# MCU_RP2350.net
KiCad netlist of a schematic drawn in Altium Designer
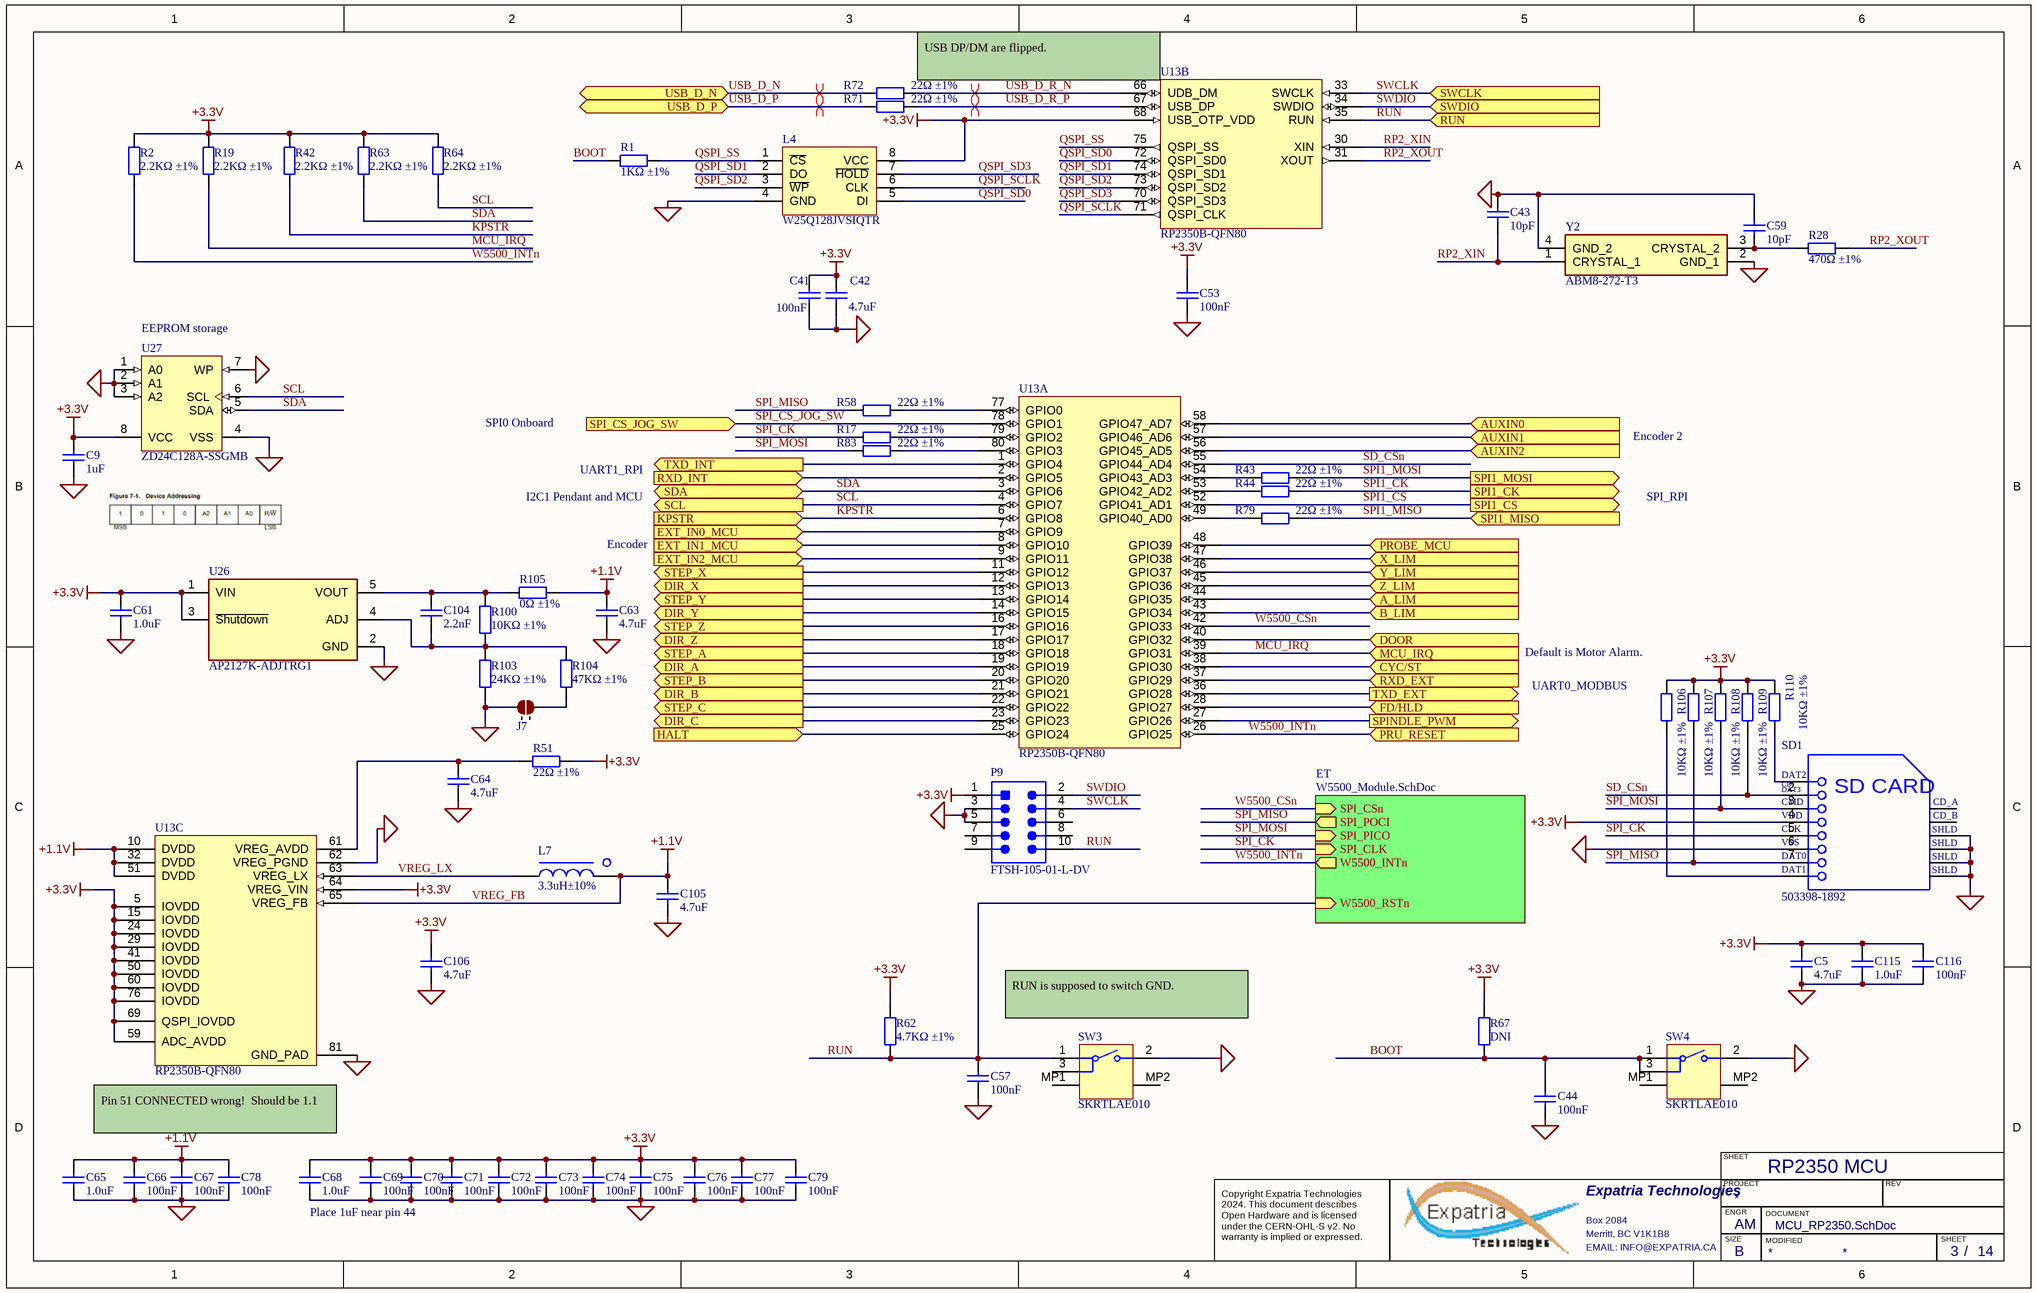
[diagram p0: MCU_RP2350.SchDoc]

(export (version "E")
  (design (tool "Eeschema 10.0.6"))
  (components
    (comp (ref "C5")
      (value "4.7uF")
      (footprint "0603_C")
      (description "16V 4.7uF X5R ±10% 0603 Multilayer Ceramic Capacitors MLCC - SMD/SMT ROHS")
      (fields (field (name "MANUFACTURER") "Samsung Electro-Mechanics") (field (name "TOLERANCE") "10%"))
      (libsource (lib "Sienci_Labs") (part "0603 4.7uF (475) 10% 16V"))
    )
    (comp (ref "C9")
      (value "1uF")
      (footprint "0603_C")
      (description "Chip capacitors")
      (fields
        (field (name "MANUFACTURER") "Samsung Electro-Mechanics")
        (field (name "PARTNUMBER") "CL10A105KB8NNNC")
      )
      (libsource (lib "Cap") (part "0603 1uF (105) 10% 50V"))
    )
    (comp (ref "C41")
      (value "100nF")
      (footprint "0402_C")
      (description "Chip capacitors")
      (fields
        (field (name "MANUFACTURER") "Samsung Electro-Mechanics")
        (field (name "PARTNUMBER") "CL05B104KO5NNNC")
      )
      (libsource (lib "Cap") (part "0402 100nF (104) 10% 16V"))
    )
    (comp (ref "C42")
      (value "4.7uF")
      (footprint "0402_C")
      (description "Chip capacitor")
      (fields
        (field (name "MANUFACTURER") "Samsung Electro-Mechanics")
        (field (name "PARTNUMBER") "CL05A475MP5NRNC")
      )
      (libsource (lib "Cap") (part "0402 4.7uF (475) 20% 10V"))
    )
    (comp (ref "C43")
      (value "10pF")
      (footprint "0402_C")
      (description "Chip capacitors")
      (fields
        (field (name "MANUFACTURER") "Samsung Electro-Mechanics")
        (field (name "PARTNUMBER") "CL05C100JB5NNNC")
      )
      (libsource (lib "Cap") (part "0402 10pF (100) 5% 50V"))
    )
    (comp (ref "C44")
      (value "100nF")
      (footprint "0402_C")
      (description "Chip capacitors")
      (fields
        (field (name "MANUFACTURER") "Samsung Electro-Mechanics")
        (field (name "PARTNUMBER") "CL05B104KO5NNNC")
      )
      (libsource (lib "Cap") (part "0402 100nF (104) 10% 16V"))
    )
    (comp (ref "C53")
      (value "100nF")
      (footprint "0402_C")
      (description "Chip capacitors")
      (fields
        (field (name "MANUFACTURER") "Samsung Electro-Mechanics")
        (field (name "PARTNUMBER") "CL05B104KO5NNNC")
      )
      (libsource (lib "Cap") (part "0402 100nF (104) 10% 16V"))
    )
    (comp (ref "C57")
      (value "100nF")
      (footprint "0402_C")
      (description "Chip capacitors")
      (fields
        (field (name "MANUFACTURER") "Samsung Electro-Mechanics")
        (field (name "PARTNUMBER") "CL05B104KO5NNNC")
      )
      (libsource (lib "Cap") (part "0402 100nF (104) 10% 16V"))
    )
    (comp (ref "C59")
      (value "10pF")
      (footprint "0402_C")
      (description "Chip capacitors")
      (fields
        (field (name "MANUFACTURER") "Samsung Electro-Mechanics")
        (field (name "PARTNUMBER") "CL05C100JB5NNNC")
      )
      (libsource (lib "Cap") (part "0402 10pF (100) 5% 50V"))
    )
    (comp (ref "C61")
      (value "1.0uF")
      (footprint "0402_C")
      (description "Chip capacitor")
      (fields
        (field (name "MANUFACTURER") "Samsung Electro-Mechanics")
        (field (name "PARTNUMBER") "CL05A105KA5NQNC")
      )
      (libsource (lib "Cap") (part "0402 1.0uF (105) 10% 25V"))
    )
    (comp (ref "C63")
      (value "4.7uF")
      (footprint "0402_C")
      (description "Chip capacitor")
      (fields
        (field (name "MANUFACTURER") "Samsung Electro-Mechanics")
        (field (name "PARTNUMBER") "CL05A475MP5NRNC")
      )
      (libsource (lib "Cap") (part "0402 4.7uF (475) 20% 10V"))
    )
    (comp (ref "C64")
      (value "4.7uF")
      (footprint "0402_C")
      (description "Chip capacitor")
      (fields
        (field (name "MANUFACTURER") "Samsung Electro-Mechanics")
        (field (name "PARTNUMBER") "CL05A475MP5NRNC")
      )
      (libsource (lib "Cap") (part "0402 4.7uF (475) 20% 10V"))
    )
    (comp (ref "C65")
      (value "1.0uF")
      (footprint "0402_C")
      (description "Chip capacitor")
      (fields
        (field (name "MANUFACTURER") "Samsung Electro-Mechanics")
        (field (name "PARTNUMBER") "CL05A105KA5NQNC")
      )
      (libsource (lib "Cap") (part "0402 1.0uF (105) 10% 25V"))
    )
    (comp (ref "C66")
      (value "100nF")
      (footprint "0402_C")
      (description "Chip capacitors")
      (fields
        (field (name "MANUFACTURER") "Samsung Electro-Mechanics")
        (field (name "PARTNUMBER") "CL05B104KO5NNNC")
      )
      (libsource (lib "Cap") (part "0402 100nF (104) 10% 16V"))
    )
    (comp (ref "C67")
      (value "100nF")
      (footprint "0402_C")
      (description "Chip capacitors")
      (fields
        (field (name "MANUFACTURER") "Samsung Electro-Mechanics")
        (field (name "PARTNUMBER") "CL05B104KO5NNNC")
      )
      (libsource (lib "Cap") (part "0402 100nF (104) 10% 16V"))
    )
    (comp (ref "C68")
      (value "1.0uF")
      (footprint "0402_C")
      (description "Chip capacitor")
      (fields
        (field (name "MANUFACTURER") "Samsung Electro-Mechanics")
        (field (name "PARTNUMBER") "CL05A105KA5NQNC")
      )
      (libsource (lib "Cap") (part "0402 1.0uF (105) 10% 25V"))
    )
    (comp (ref "C69")
      (value "100nF")
      (footprint "0402_C")
      (description "Chip capacitors")
      (fields
        (field (name "MANUFACTURER") "Samsung Electro-Mechanics")
        (field (name "PARTNUMBER") "CL05B104KO5NNNC")
      )
      (libsource (lib "Cap") (part "0402 100nF (104) 10% 16V"))
    )
    (comp (ref "C70")
      (value "100nF")
      (footprint "0402_C")
      (description "Chip capacitors")
      (fields
        (field (name "MANUFACTURER") "Samsung Electro-Mechanics")
        (field (name "PARTNUMBER") "CL05B104KO5NNNC")
      )
      (libsource (lib "Cap") (part "0402 100nF (104) 10% 16V"))
    )
    (comp (ref "C71")
      (value "100nF")
      (footprint "0402_C")
      (description "Chip capacitors")
      (fields
        (field (name "MANUFACTURER") "Samsung Electro-Mechanics")
        (field (name "PARTNUMBER") "CL05B104KO5NNNC")
      )
      (libsource (lib "Cap") (part "0402 100nF (104) 10% 16V"))
    )
    (comp (ref "C72")
      (value "100nF")
      (footprint "0402_C")
      (description "Chip capacitors")
      (fields
        (field (name "MANUFACTURER") "Samsung Electro-Mechanics")
        (field (name "PARTNUMBER") "CL05B104KO5NNNC")
      )
      (libsource (lib "Cap") (part "0402 100nF (104) 10% 16V"))
    )
    (comp (ref "C73")
      (value "100nF")
      (footprint "0402_C")
      (description "Chip capacitors")
      (fields
        (field (name "MANUFACTURER") "Samsung Electro-Mechanics")
        (field (name "PARTNUMBER") "CL05B104KO5NNNC")
      )
      (libsource (lib "Cap") (part "0402 100nF (104) 10% 16V"))
    )
    (comp (ref "C74")
      (value "100nF")
      (footprint "0402_C")
      (description "Chip capacitors")
      (fields
        (field (name "MANUFACTURER") "Samsung Electro-Mechanics")
        (field (name "PARTNUMBER") "CL05B104KO5NNNC")
      )
      (libsource (lib "Cap") (part "0402 100nF (104) 10% 16V"))
    )
    (comp (ref "C75")
      (value "100nF")
      (footprint "0402_C")
      (description "Chip capacitors")
      (fields
        (field (name "MANUFACTURER") "Samsung Electro-Mechanics")
        (field (name "PARTNUMBER") "CL05B104KO5NNNC")
      )
      (libsource (lib "Cap") (part "0402 100nF (104) 10% 16V"))
    )
    (comp (ref "C76")
      (value "100nF")
      (footprint "0402_C")
      (description "Chip capacitors")
      (fields
        (field (name "MANUFACTURER") "Samsung Electro-Mechanics")
        (field (name "PARTNUMBER") "CL05B104KO5NNNC")
      )
      (libsource (lib "Cap") (part "0402 100nF (104) 10% 16V"))
    )
    (comp (ref "C77")
      (value "100nF")
      (footprint "0402_C")
      (description "Chip capacitors")
      (fields
        (field (name "MANUFACTURER") "Samsung Electro-Mechanics")
        (field (name "PARTNUMBER") "CL05B104KO5NNNC")
      )
      (libsource (lib "Cap") (part "0402 100nF (104) 10% 16V"))
    )
    (comp (ref "C78")
      (value "100nF")
      (footprint "0402_C")
      (description "Chip capacitors")
      (fields
        (field (name "MANUFACTURER") "Samsung Electro-Mechanics")
        (field (name "PARTNUMBER") "CL05B104KO5NNNC")
      )
      (libsource (lib "Cap") (part "0402 100nF (104) 10% 16V"))
    )
    (comp (ref "C79")
      (value "100nF")
      (footprint "0402_C")
      (description "Chip capacitors")
      (fields
        (field (name "MANUFACTURER") "Samsung Electro-Mechanics")
        (field (name "PARTNUMBER") "CL05B104KO5NNNC")
      )
      (libsource (lib "Cap") (part "0402 100nF (104) 10% 16V"))
    )
    (comp (ref "C104")
      (value "2.2nF")
      (footprint "0402_C")
      (description "Chip capacitor")
      (fields
        (field (name "MANUFACTURER") "Guangdong Fenghua Advanced Tech")
        (field (name "PARTNUMBER") "0402B222K500NT")
      )
      (libsource (lib "Cap") (part "0402 2.2nF (222) 10% 50V"))
    )
    (comp (ref "C105")
      (value "4.7uF")
      (footprint "0402_C - wide")
      (description "Chip capacitor")
      (fields
        (field (name "MANUFACTURER") "Samsung Electro-Mechanics")
        (field (name "PARTNUMBER") "CL05A475MP5NRNC")
      )
      (libsource (lib "Cap") (part "0402 4.7uF (475) 20% 10V"))
    )
    (comp (ref "C106")
      (value "4.7uF")
      (footprint "0402_C - wide")
      (description "Chip capacitor")
      (fields
        (field (name "MANUFACTURER") "Samsung Electro-Mechanics")
        (field (name "PARTNUMBER") "CL05A475MP5NRNC")
      )
      (libsource (lib "Cap") (part "0402 4.7uF (475) 20% 10V"))
    )
    (comp (ref "C115")
      (value "1.0uF")
      (footprint "0402_C")
      (description "Chip capacitor")
      (fields (field (name "MANUFACTURER") "Samsung Electro-Mechanics") (field (name "TOLERANCE") "10%"))
      (libsource (lib "Cap") (part "0402 1.0uF (105) 10% 25V"))
    )
    (comp (ref "C116")
      (value "100nF")
      (footprint "0402_C")
      (description "16V 100nF X7R ±10% 0402 Multilayer Ceramic Capacitors MLCC - SMD/SMT ROHS")
      (fields (field (name "MANUFACTURER") "Samsung Electro-Mechanics") (field (name "TOLERANCE") "10%"))
      (libsource (lib "Sienci_Labs") (part "0402 100nF (104) 10% 16V"))
    )
    (comp (ref "J7")
      (value "2 way net solder junction - Normally Open")
      (footprint "2waySolder_NO")
      (libsource (lib "NetTie") (part "2waySolderNO"))
    )
    (comp (ref "L4")
      (value "W25Q128JVSIQTR")
      (footprint "SOIC-8_208mil")
      (description "Flash ROM")
      (libsource (lib "IC") (part "W25Q128JVSIQTR_[C97521]"))
    )
    (comp (ref "L7")
      (value "3.3uH±10%")
      (footprint "0806_L_POL")
      (description "贴片电感")
      (libsource (lib "IUD") (part "0806 3.3uH Polarized RP2350"))
    )
    (comp (ref "P9")
      (value "FTSH-105-01-L-DV")
      (footprint "SMTC-FTSH-105-01-L-DV_V")
      (description "Male Header, Pitch 1.27 mm, 2 x 5 Position, Height 5.96 mm, -55 to 125 degC, RoHS, Bulk")
      (fields (field (name "MANUFACTURER") "Samtec"))
      (libsource (lib "Altium Content Vault") (part "CN-2P-M-R10"))
    )
    (comp (ref "R1")
      (value "1KΩ ±1%")
      (footprint "0402_R")
      (description "Chip resistor")
      (fields (field (name "MANUFACTURER") "Uniroyal Elec") (field (name "PARTNUMBER") "0402WGF1001TCE"))
      (libsource (lib "RES") (part "0402 1K (1001) 1%"))
    )
    (comp (ref "R2")
      (value "2.2KΩ ±1%")
      (footprint "0402_R")
      (description "Chip resistor")
      (fields (field (name "MANUFACTURER") "Uniroyal Elec") (field (name "PARTNUMBER") "0402WGF2201TCE"))
      (libsource (lib "RES") (part "0402 2.2K (2201) 1%"))
    )
    (comp (ref "R17")
      (value "22Ω ±1%")
      (footprint "0402_R")
      (description "Chip resistor")
      (fields (field (name "MANUFACTURER") "Uniroyal Elec") (field (name "PARTNUMBER") "0402WGF220JTCE"))
      (libsource (lib "") (part "0402 22R (22R0) 1%_2"))
    )
    (comp (ref "R19")
      (value "2.2KΩ ±1%")
      (footprint "0402_R")
      (description "Chip resistor")
      (fields (field (name "MANUFACTURER") "Uniroyal Elec") (field (name "PARTNUMBER") "0402WGF2201TCE"))
      (libsource (lib "RES") (part "0402 2.2K (2201) 1%"))
    )
    (comp (ref "R28")
      (value "470Ω ±1%")
      (footprint "0402_R")
      (description "Chip resistor")
      (fields (field (name "MANUFACTURER") "Uniroyal Elec") (field (name "PARTNUMBER") "0402WGF4700TCE"))
      (libsource (lib "RES") (part "0402 470R (4700) 1%"))
    )
    (comp (ref "R42")
      (value "2.2KΩ ±1%")
      (footprint "0402_R")
      (description "Chip resistor")
      (fields (field (name "MANUFACTURER") "Uniroyal Elec") (field (name "PARTNUMBER") "0402WGF2201TCE"))
      (libsource (lib "RES") (part "0402 2.2K (2201) 1%"))
    )
    (comp (ref "R43")
      (value "22Ω ±1%")
      (footprint "0402_R")
      (description "Chip resistor")
      (fields (field (name "MANUFACTURER") "Uniroyal Elec") (field (name "PARTNUMBER") "0402WGF220JTCE"))
      (libsource (lib "") (part "0402 22R (22R0) 1%_2"))
    )
    (comp (ref "R44")
      (value "22Ω ±1%")
      (footprint "0402_R")
      (description "Chip resistor")
      (fields (field (name "MANUFACTURER") "Uniroyal Elec") (field (name "PARTNUMBER") "0402WGF220JTCE"))
      (libsource (lib "") (part "0402 22R (22R0) 1%_2"))
    )
    (comp (ref "R51")
      (value "22Ω ±1%")
      (footprint "0402_R")
      (description "Chip resistor")
      (fields (field (name "MANUFACTURER") "Uniroyal Elec") (field (name "PARTNUMBER") "0402WGF220JTCE"))
      (libsource (lib "RES") (part "0402 22R (22R0) 1%"))
    )
    (comp (ref "R58")
      (value "22Ω ±1%")
      (footprint "0402_R")
      (description "Chip resistor")
      (fields (field (name "MANUFACTURER") "Uniroyal Elec") (field (name "PARTNUMBER") "0402WGF220JTCE"))
      (libsource (lib "") (part "0402 22R (22R0) 1%_2"))
    )
    (comp (ref "R62")
      (value "4.7KΩ ±1%")
      (footprint "0402_R")
      (description "Chip resistor")
      (fields (field (name "MANUFACTURER") "Uniroyal Elec") (field (name "PARTNUMBER") "0402WGF4701TCE"))
      (libsource (lib "RES") (part "0402 4.7K (4701) 1%"))
    )
    (comp (ref "R63")
      (value "2.2KΩ ±1%")
      (footprint "0402_R")
      (description "Chip resistor")
      (fields (field (name "MANUFACTURER") "Uniroyal Elec") (field (name "PARTNUMBER") "0402WGF2201TCE"))
      (libsource (lib "RES") (part "0402 2.2K (2201) 1%"))
    )
    (comp (ref "R64")
      (value "2.2KΩ ±1%")
      (footprint "0402_R")
      (description "Chip resistor")
      (fields (field (name "MANUFACTURER") "Uniroyal Elec") (field (name "PARTNUMBER") "0402WGF2201TCE"))
      (libsource (lib "RES") (part "0402 2.2K (2201) 1%"))
    )
    (comp (ref "R67")
      (value "DNI")
      (footprint "0603_R")
      (description "Chip resistor")
      (fields (field (name "MANUFACTURER") "Uniroyal Elec") (field (name "PARTNUMBER") "0603WAF1002T5E"))
      (libsource (lib "RES") (part "0603 10K (1002) 1%"))
    )
    (comp (ref "R71")
      (value "22Ω ±1%")
      (footprint "0402_R")
      (description "Chip resistor")
      (fields (field (name "MANUFACTURER") "Uniroyal Elec") (field (name "PARTNUMBER") "0402WGF220JTCE"))
      (libsource (lib "") (part "0402 22R (22R0) 1%_1"))
    )
    (comp (ref "R72")
      (value "22Ω ±1%")
      (footprint "0402_R")
      (description "Chip resistor")
      (fields (field (name "MANUFACTURER") "Uniroyal Elec") (field (name "PARTNUMBER") "0402WGF220JTCE"))
      (libsource (lib "") (part "0402 22R (22R0) 1%_1"))
    )
    (comp (ref "R79")
      (value "22Ω ±1%")
      (footprint "0402_R")
      (description "Chip resistor")
      (fields (field (name "MANUFACTURER") "Uniroyal Elec") (field (name "PARTNUMBER") "0402WGF220JTCE"))
      (libsource (lib "") (part "0402 22R (22R0) 1%_2"))
    )
    (comp (ref "R83")
      (value "22Ω ±1%")
      (footprint "0402_R")
      (description "Chip resistor")
      (fields (field (name "MANUFACTURER") "Uniroyal Elec") (field (name "PARTNUMBER") "0402WGF220JTCE"))
      (libsource (lib "") (part "0402 22R (22R0) 1%_2"))
    )
    (comp (ref "R100")
      (value "10KΩ ±1%")
      (footprint "0402_R")
      (description "Chip resistor")
      (fields (field (name "MANUFACTURER") "Uniroyal Elec") (field (name "PARTNUMBER") "0402WGF1002TCE"))
      (libsource (lib "RES") (part "0402 10K (1002) 1%"))
    )
    (comp (ref "R103")
      (value "24KΩ ±1%")
      (footprint "0402_R")
      (description "Chip resistor")
      (fields (field (name "MANUFACTURER") "Uniroyal Elec") (field (name "PARTNUMBER") "0402WGF2402TCE"))
      (libsource (lib "RES") (part "0402 24K (2402) 1%"))
    )
    (comp (ref "R104")
      (value "47KΩ ±1%")
      (footprint "0402_R")
      (description "Chip resistor")
      (fields (field (name "MANUFACTURER") "Uniroyal Elec") (field (name "PARTNUMBER") "0402WGF4702TCE"))
      (libsource (lib "RES") (part "0402 47K (4702) 1%"))
    )
    (comp (ref "R105")
      (value "0Ω ±1%")
      (footprint "0402_R")
      (description "Chip resistor")
      (fields (field (name "MANUFACTURER") "Uniroyal Elec") (field (name "PARTNUMBER") "0402WGF0000TCE"))
      (libsource (lib "RES") (part "0402 0R (0R0) 1%"))
    )
    (comp (ref "R106")
      (value "10KΩ ±1%")
      (footprint "0402_R")
      (description "Chip resistor")
      (fields (field (name "MANUFACTURER") "Uniroyal Elec") (field (name "PARTNUMBER") "0402WGF1002TCE"))
      (libsource (lib "RES") (part "0402 10K (1002) 1%"))
    )
    (comp (ref "R107")
      (value "10KΩ ±1%")
      (footprint "0402_R")
      (description "Chip resistor")
      (fields (field (name "MANUFACTURER") "Uniroyal Elec") (field (name "PARTNUMBER") "0402WGF1002TCE"))
      (libsource (lib "RES") (part "0402 10K (1002) 1%"))
    )
    (comp (ref "R108")
      (value "10KΩ ±1%")
      (footprint "0402_R")
      (description "Chip resistor")
      (fields (field (name "MANUFACTURER") "Uniroyal Elec") (field (name "PARTNUMBER") "0402WGF1002TCE"))
      (libsource (lib "RES") (part "0402 10K (1002) 1%"))
    )
    (comp (ref "R109")
      (value "10KΩ ±1%")
      (footprint "0402_R")
      (description "Chip resistor")
      (fields (field (name "MANUFACTURER") "Uniroyal Elec") (field (name "PARTNUMBER") "0402WGF1002TCE"))
      (libsource (lib "RES") (part "0402 10K (1002) 1%"))
    )
    (comp (ref "R110")
      (value "10KΩ ±1%")
      (footprint "0402_R")
      (description "Chip resistor")
      (fields (field (name "MANUFACTURER") "Uniroyal Elec") (field (name "PARTNUMBER") "0402WGF1002TCE"))
      (libsource (lib "RES") (part "0402 10K (1002) 1%"))
    )
    (comp (ref "SD1")
      (value "503398-1892")
      (footprint "MOLX-503398-1892_V")
      (description "Micro SD Connector, Pitch 1.1 mm, 8 Position, Height 1.4 mm, -25 to 85 degC, RoHS, Tape and Reel")
      (fields (field (name "MANUFACTURER") "Molex"))
      (libsource (lib "Altium Content Vault") (part "CN-SD-8-2SW-4S"))
    )
    (comp (ref "SW3")
      (value "SKRTLAE010")
      (footprint "ALPS-SKRTLAE010_V")
      (description "Side Push Type, 250 V, -40 to 90 degC, 3-Pin SMD, RoHS, Tape and Reel")
      (fields (field (name "MANUFACTURER") "ALPS"))
      (libsource (lib "Altium Content Vault") (part "SW_SPST-3_A"))
    )
    (comp (ref "SW4")
      (value "SKRTLAE010")
      (footprint "ALPS-SKRTLAE010_V")
      (description "Side Push Type, 250 V, -40 to 90 degC, 3-Pin SMD, RoHS, Tape and Reel")
      (fields (field (name "MANUFACTURER") "ALPS"))
      (libsource (lib "Altium Content Vault") (part "SW_SPST-3_A"))
    )
    (comp (ref "U13")
      (value "RP2350B-QFN80")
      (footprint "RP2350B-QFN80")
      (description "Second MCU from RPI")
      (libsource (lib "Universal_CNC_Breakout") (part "RP2350B-QFN80"))
    )
    (comp (ref "U26")
      (value "AP2127K-ADJTRG1")
      (footprint "FP-SOT25-MFG")
      (description "IC REG LIN POS ADJ 300MA SOT23-5")
      (fields
        (field (name "MANUFACTURER") "Diodes Inc.")
        (field (name "OCTOPART") "https://octopart.com/ap2127k-adjtrg1-diodes+inc.-30954599")
      )
      (libsource (lib "Altium Content Vault") (part "78625ba3b6c55e3ed088d444736afd9"))
    )
    (comp (ref "U27")
      (value "ZD24C128A-SSGMB")
      (footprint "SOIC-SN8_L")
      (description "IC EEPROM 128KBIT I2C 8SOIC")
      (libsource (lib "PrintNC_GRBLHAL_Breakout") (part "MEM-SEEPROM-34AA02-IL8"))
    )
    (comp (ref "Y2")
      (value "ABM8-272-T3")
      (footprint "YSX321SL")
      (description "Crystal or Oscillator 12MHz RP2350")
      (libsource (lib "*") (part "YSX321SL"))
    )
  )
  (nets
    (net (code "1") (name "+1.1V") (class "Default")
      (node (ref "C105") (pin "2") (pinfunction "2_2") (pintype "passive"))
      (node (ref "C63") (pin "2") (pinfunction "2_2") (pintype "passive"))
      (node (ref "C65") (pin "2") (pinfunction "2_2") (pintype "passive"))
      (node (ref "C66") (pin "2") (pinfunction "2_2") (pintype "passive"))
      (node (ref "C67") (pin "2") (pinfunction "2_2") (pintype "passive"))
      (node (ref "C78") (pin "2") (pinfunction "2_2") (pintype "passive"))
      (node (ref "L7") (pin "2") (pinfunction "2_2") (pintype "passive"))
      (node (ref "R105") (pin "2") (pinfunction "2_2") (pintype "passive"))
      (node (ref "U13") (pin "10") (pinfunction "DVDD_10") (pintype "passive"))
      (node (ref "U13") (pin "32") (pinfunction "DVDD_32") (pintype "passive"))
      (node (ref "U13") (pin "51") (pinfunction "DVDD_51") (pintype "passive"))
      (node (ref "U13") (pin "65") (pinfunction "VREG_FB_65") (pintype "input"))
    )
    (net (code "2") (name "+3.3V") (class "Default")
      (node (ref "C106") (pin "2") (pinfunction "2_2") (pintype "passive"))
      (node (ref "C115") (pin "2") (pinfunction "2_2") (pintype "passive"))
      (node (ref "C116") (pin "2") (pinfunction "2_2") (pintype "passive"))
      (node (ref "C41") (pin "2") (pinfunction "2_2") (pintype "passive"))
      (node (ref "C42") (pin "2") (pinfunction "2_2") (pintype "passive"))
      (node (ref "C5") (pin "2") (pinfunction "2_2") (pintype "passive"))
      (node (ref "C53") (pin "2") (pinfunction "2_2") (pintype "passive"))
      (node (ref "C61") (pin "2") (pinfunction "2_2") (pintype "passive"))
      (node (ref "C68") (pin "2") (pinfunction "2_2") (pintype "passive"))
      (node (ref "C69") (pin "2") (pinfunction "2_2") (pintype "passive"))
      (node (ref "C70") (pin "2") (pinfunction "2_2") (pintype "passive"))
      (node (ref "C71") (pin "2") (pinfunction "2_2") (pintype "passive"))
      (node (ref "C72") (pin "2") (pinfunction "2_2") (pintype "passive"))
      (node (ref "C73") (pin "2") (pinfunction "2_2") (pintype "passive"))
      (node (ref "C74") (pin "2") (pinfunction "2_2") (pintype "passive"))
      (node (ref "C75") (pin "2") (pinfunction "2_2") (pintype "passive"))
      (node (ref "C76") (pin "2") (pinfunction "2_2") (pintype "passive"))
      (node (ref "C77") (pin "2") (pinfunction "2_2") (pintype "passive"))
      (node (ref "C79") (pin "2") (pinfunction "2_2") (pintype "passive"))
      (node (ref "C9") (pin "2") (pinfunction "2_2") (pintype "passive"))
      (node (ref "L4") (pin "8") (pinfunction "VCC_8") (pintype "passive"))
      (node (ref "P9") (pin "1") (pinfunction "1_1") (pintype "passive"))
      (node (ref "R106") (pin "2") (pinfunction "2_2") (pintype "passive"))
      (node (ref "R107") (pin "2") (pinfunction "2_2") (pintype "passive"))
      (node (ref "R108") (pin "2") (pinfunction "2_2") (pintype "passive"))
      (node (ref "R109") (pin "2") (pinfunction "2_2") (pintype "passive"))
      (node (ref "R110") (pin "2") (pinfunction "2_2") (pintype "passive"))
      (node (ref "R19") (pin "2") (pinfunction "2_2") (pintype "passive"))
      (node (ref "R2") (pin "2") (pinfunction "2_2") (pintype "passive"))
      (node (ref "R42") (pin "2") (pinfunction "2_2") (pintype "passive"))
      (node (ref "R51") (pin "2") (pinfunction "2_2") (pintype "passive"))
      (node (ref "R62") (pin "2") (pinfunction "2_2") (pintype "passive"))
      (node (ref "R63") (pin "2") (pinfunction "2_2") (pintype "passive"))
      (node (ref "R64") (pin "2") (pinfunction "2_2") (pintype "passive"))
      (node (ref "R67") (pin "1") (pinfunction "1_1") (pintype "passive"))
      (node (ref "SD1") (pin "4") (pinfunction "VDD_4") (pintype "passive"))
      (node (ref "U13") (pin "15") (pinfunction "IOVDD_15") (pintype "passive"))
      (node (ref "U13") (pin "24") (pinfunction "IOVDD_24") (pintype "passive"))
      (node (ref "U13") (pin "29") (pinfunction "IOVDD_29") (pintype "passive"))
      (node (ref "U13") (pin "41") (pinfunction "IOVDD_41") (pintype "passive"))
      (node (ref "U13") (pin "5") (pinfunction "IOVDD_5") (pintype "passive"))
      (node (ref "U13") (pin "50") (pinfunction "IOVDD_50") (pintype "passive"))
      (node (ref "U13") (pin "59") (pinfunction "ADC_AVDD_59") (pintype "passive"))
      (node (ref "U13") (pin "60") (pinfunction "IOVDD_60") (pintype "passive"))
      (node (ref "U13") (pin "64") (pinfunction "VREG_VIN_64") (pintype "input"))
      (node (ref "U13") (pin "68") (pinfunction "USB_OTP_VDD_68") (pintype "input"))
      (node (ref "U13") (pin "69") (pinfunction "QSPI_IOVDD_69") (pintype "passive"))
      (node (ref "U13") (pin "76") (pinfunction "IOVDD_76") (pintype "passive"))
      (node (ref "U26") (pin "1") (pinfunction "VIN_1") (pintype "power_in"))
      (node (ref "U26") (pin "3") (pinfunction "~{Shutdown}_3") (pintype "passive"))
      (node (ref "U27") (pin "8") (pinfunction "VCC_8") (pintype "power_in"))
    )
    (net (code "3") (name "/AUXIN0") (class "Default")
      (node (ref "U13") (pin "58") (pinfunction "GPIO47_AD7_58") (pintype "bidirectional"))
    )
    (net (code "4") (name "/AUXIN1") (class "Default")
      (node (ref "U13") (pin "57") (pinfunction "GPIO46_AD6_57") (pintype "bidirectional"))
    )
    (net (code "5") (name "/AUXIN2") (class "Default")
      (node (ref "U13") (pin "56") (pinfunction "GPIO45_AD5_56") (pintype "bidirectional"))
    )
    (net (code "6") (name "/A_LIM") (class "Default")
      (node (ref "U13") (pin "44") (pinfunction "GPIO35_44") (pintype "bidirectional"))
    )
    (net (code "7") (name "/BOOT") (class "Default")
      (node (ref "C44") (pin "2") (pinfunction "2_2") (pintype "passive"))
      (node (ref "R1") (pin "1") (pinfunction "1_1") (pintype "passive"))
      (node (ref "R67") (pin "2") (pinfunction "2_2") (pintype "passive"))
      (node (ref "SW4") (pin "1") (pinfunction "1_1") (pintype "passive"))
      (node (ref "SW4") (pin "3") (pinfunction "3_3") (pintype "passive"))
    )
    (net (code "8") (name "/B_LIM") (class "Default")
      (node (ref "U13") (pin "43") (pinfunction "GPIO34_43") (pintype "bidirectional"))
    )
    (net (code "9") (name "/CYC{slash}ST") (class "Default")
      (node (ref "U13") (pin "38") (pinfunction "GPIO30_38") (pintype "bidirectional"))
    )
    (net (code "10") (name "/DIR_A") (class "Default")
      (node (ref "U13") (pin "19") (pinfunction "GPIO19_19") (pintype "bidirectional"))
    )
    (net (code "11") (name "/DIR_B") (class "Default")
      (node (ref "U13") (pin "21") (pinfunction "GPIO21_21") (pintype "bidirectional"))
    )
    (net (code "12") (name "/DIR_C") (class "Default")
      (node (ref "U13") (pin "23") (pinfunction "GPIO23_23") (pintype "bidirectional"))
    )
    (net (code "13") (name "/DIR_X") (class "Default")
      (node (ref "U13") (pin "12") (pinfunction "GPIO13_12") (pintype "bidirectional"))
    )
    (net (code "14") (name "/DIR_Y") (class "Default")
      (node (ref "U13") (pin "14") (pinfunction "GPIO15_14") (pintype "bidirectional"))
    )
    (net (code "15") (name "/DIR_Z") (class "Default")
      (node (ref "U13") (pin "17") (pinfunction "GPIO17_17") (pintype "bidirectional"))
    )
    (net (code "16") (name "/DOOR") (class "Default")
      (node (ref "U13") (pin "40") (pinfunction "GPIO32_40") (pintype "bidirectional"))
    )
    (net (code "17") (name "/EXT_IN0_MCU") (class "Default")
      (node (ref "U13") (pin "7") (pinfunction "GPIO9_7") (pintype "bidirectional"))
    )
    (net (code "18") (name "/EXT_IN1_MCU") (class "Default")
      (node (ref "U13") (pin "8") (pinfunction "GPIO10_8") (pintype "bidirectional"))
    )
    (net (code "19") (name "/EXT_IN2_MCU") (class "Default")
      (node (ref "U13") (pin "9") (pinfunction "GPIO11_9") (pintype "bidirectional"))
    )
    (net (code "20") (name "/FD{slash}HLD") (class "Default")
      (node (ref "U13") (pin "28") (pinfunction "GPIO27_28") (pintype "bidirectional"))
    )
    (net (code "21") (name "/HALT") (class "Default")
      (node (ref "U13") (pin "25") (pinfunction "GPIO24_25") (pintype "bidirectional"))
    )
    (net (code "22") (name "/KPSTR") (class "Default")
      (node (ref "R42") (pin "1") (pinfunction "1_1") (pintype "passive"))
      (node (ref "U13") (pin "6") (pinfunction "GPIO8_6") (pintype "bidirectional"))
    )
    (net (code "23") (name "/MCU_IRQ") (class "Default")
      (node (ref "R19") (pin "1") (pinfunction "1_1") (pintype "passive"))
      (node (ref "U13") (pin "39") (pinfunction "GPIO31_39") (pintype "bidirectional"))
    )
    (net (code "24") (name "/PROBE_MCU") (class "Default")
      (node (ref "U13") (pin "48") (pinfunction "GPIO39_48") (pintype "bidirectional"))
    )
    (net (code "25") (name "/QSPI_SCLK") (class "Default")
      (node (ref "L4") (pin "6") (pinfunction "CLK_6") (pintype "passive"))
      (node (ref "U13") (pin "71") (pinfunction "QSPI_CLK_71") (pintype "output"))
    )
    (net (code "26") (name "/QSPI_SD0") (class "Default")
      (node (ref "L4") (pin "5") (pinfunction "DI_5") (pintype "passive"))
      (node (ref "U13") (pin "72") (pinfunction "QSPI_SD0_72") (pintype "bidirectional"))
    )
    (net (code "27") (name "/QSPI_SD1") (class "Default")
      (node (ref "L4") (pin "2") (pinfunction "DO_2") (pintype "passive"))
      (node (ref "U13") (pin "74") (pinfunction "QSPI_SD1_74") (pintype "bidirectional"))
    )
    (net (code "28") (name "/QSPI_SD2") (class "Default")
      (node (ref "L4") (pin "3") (pinfunction "~{WP}_3") (pintype "passive"))
      (node (ref "U13") (pin "73") (pinfunction "QSPI_SD2_73") (pintype "bidirectional"))
    )
    (net (code "29") (name "/QSPI_SD3") (class "Default")
      (node (ref "L4") (pin "7") (pinfunction "~{HOLD}_7") (pintype "passive"))
      (node (ref "U13") (pin "70") (pinfunction "QSPI_SD3_70") (pintype "bidirectional"))
    )
    (net (code "30") (name "/QSPI_SS") (class "Default")
      (node (ref "L4") (pin "1") (pinfunction "~{CS}_1") (pintype "passive"))
      (node (ref "R1") (pin "2") (pinfunction "2_2") (pintype "passive"))
      (node (ref "U13") (pin "75") (pinfunction "QSPI_SS_75") (pintype "output"))
    )
    (net (code "31") (name "/RP2_XIN") (class "Default")
      (node (ref "C43") (pin "1") (pinfunction "1_1") (pintype "passive"))
      (node (ref "U13") (pin "30") (pinfunction "XIN_30") (pintype "input"))
      (node (ref "Y2") (pin "1") (pinfunction "CRYSTAL_1_1") (pintype "passive"))
    )
    (net (code "32") (name "/RP2_XOUT") (class "Default")
      (node (ref "R28") (pin "2") (pinfunction "2_2") (pintype "passive"))
      (node (ref "U13") (pin "31") (pinfunction "XOUT_31") (pintype "output"))
    )
    (net (code "33") (name "/RUN") (class "Default")
      (node (ref "C57") (pin "2") (pinfunction "2_2") (pintype "passive"))
      (node (ref "P9") (pin "10") (pinfunction "10_10") (pintype "passive"))
      (node (ref "R62") (pin "1") (pinfunction "1_1") (pintype "passive"))
      (node (ref "SW3") (pin "1") (pinfunction "1_1") (pintype "passive"))
      (node (ref "U13") (pin "35") (pinfunction "RUN_35") (pintype "input"))
    )
    (net (code "34") (name "/RXD_EXT") (class "Default")
      (node (ref "U13") (pin "37") (pinfunction "GPIO29_37") (pintype "bidirectional"))
    )
    (net (code "35") (name "/RXD_INT") (class "Default")
      (node (ref "U13") (pin "2") (pinfunction "GPIO5_2") (pintype "bidirectional"))
    )
    (net (code "36") (name "/SCL") (class "Default")
      (node (ref "R64") (pin "1") (pinfunction "1_1") (pintype "passive"))
      (node (ref "U13") (pin "4") (pinfunction "GPIO7_4") (pintype "bidirectional"))
      (node (ref "U27") (pin "6") (pinfunction "SCL_6") (pintype "input"))
    )
    (net (code "37") (name "/SDA") (class "Default")
      (node (ref "R63") (pin "1") (pinfunction "1_1") (pintype "passive"))
      (node (ref "U13") (pin "3") (pinfunction "GPIO6_3") (pintype "bidirectional"))
      (node (ref "U27") (pin "5") (pinfunction "SDA_5") (pintype "bidirectional"))
    )
    (net (code "38") (name "/SD_CSn") (class "Default")
      (node (ref "R109") (pin "1") (pinfunction "1_1") (pintype "passive"))
      (node (ref "SD1") (pin "2") (pinfunction "CD/DAT3_2") (pintype "passive"))
      (node (ref "U13") (pin "55") (pinfunction "GPIO44_AD4_55") (pintype "bidirectional"))
    )
    (net (code "39") (name "/SPI1_CK") (class "Default")
      (node (ref "R44") (pin "1") (pinfunction "1_1") (pintype "passive"))
    )
    (net (code "40") (name "/SPI1_CS") (class "Default")
      (node (ref "U13") (pin "52") (pinfunction "GPIO41_AD1_52") (pintype "bidirectional"))
    )
    (net (code "41") (name "/SPI1_MISO") (class "Default")
      (node (ref "R79") (pin "1") (pinfunction "1_1") (pintype "passive"))
    )
    (net (code "42") (name "/SPI1_MOSI") (class "Default")
      (node (ref "R43") (pin "1") (pinfunction "1_1") (pintype "passive"))
    )
    (net (code "43") (name "/SPINDLE_PWM") (class "Default")
      (node (ref "U13") (pin "27") (pinfunction "GPIO26_27") (pintype "bidirectional"))
    )
    (net (code "44") (name "/SPI_CK") (class "Default")
      (node (ref "R17") (pin "2") (pinfunction "2_2") (pintype "passive"))
      (node (ref "SD1") (pin "5") (pinfunction "CLK_5") (pintype "passive"))
    )
    (net (code "45") (name "/SPI_CS_JOG_SW") (class "Default")
      (node (ref "U13") (pin "78") (pinfunction "GPIO1_78") (pintype "bidirectional"))
    )
    (net (code "46") (name "/SPI_MISO") (class "Default")
      (node (ref "R107") (pin "1") (pinfunction "1_1") (pintype "passive"))
      (node (ref "R58") (pin "2") (pinfunction "2_2") (pintype "passive"))
      (node (ref "SD1") (pin "7") (pinfunction "DAT0_7") (pintype "passive"))
    )
    (net (code "47") (name "/SPI_MOSI") (class "Default")
      (node (ref "R108") (pin "1") (pinfunction "1_1") (pintype "passive"))
      (node (ref "R83") (pin "2") (pinfunction "2_2") (pintype "passive"))
      (node (ref "SD1") (pin "3") (pinfunction "CMD_3") (pintype "passive"))
    )
    (net (code "48") (name "/STEP_A") (class "Default")
      (node (ref "U13") (pin "18") (pinfunction "GPIO18_18") (pintype "bidirectional"))
    )
    (net (code "49") (name "/STEP_B") (class "Default")
      (node (ref "U13") (pin "20") (pinfunction "GPIO20_20") (pintype "bidirectional"))
    )
    (net (code "50") (name "/STEP_C") (class "Default")
      (node (ref "U13") (pin "22") (pinfunction "GPIO22_22") (pintype "bidirectional"))
    )
    (net (code "51") (name "/STEP_X") (class "Default")
      (node (ref "U13") (pin "11") (pinfunction "GPIO12_11") (pintype "bidirectional"))
    )
    (net (code "52") (name "/STEP_Y") (class "Default")
      (node (ref "U13") (pin "13") (pinfunction "GPIO14_13") (pintype "bidirectional"))
    )
    (net (code "53") (name "/STEP_Z") (class "Default")
      (node (ref "U13") (pin "16") (pinfunction "GPIO16_16") (pintype "bidirectional"))
    )
    (net (code "54") (name "/SWCLK") (class "Default")
      (node (ref "P9") (pin "4") (pinfunction "4_4") (pintype "passive"))
      (node (ref "U13") (pin "33") (pinfunction "SWCLK_33") (pintype "input"))
    )
    (net (code "55") (name "/SWDIO") (class "Default")
      (node (ref "P9") (pin "2") (pinfunction "2_2") (pintype "passive"))
      (node (ref "U13") (pin "34") (pinfunction "SWDIO_34") (pintype "bidirectional"))
    )
    (net (code "56") (name "/TXD_EXT") (class "Default")
      (node (ref "U13") (pin "36") (pinfunction "GPIO28_36") (pintype "bidirectional"))
    )
    (net (code "57") (name "/TXD_INT") (class "Default")
      (node (ref "U13") (pin "1") (pinfunction "GPIO4_1") (pintype "bidirectional"))
    )
    (net (code "58") (name "/USB_D_N") (class "Default")
      (node (ref "R72") (pin "2") (pinfunction "2_2") (pintype "passive"))
    )
    (net (code "59") (name "/USB_D_P") (class "Default")
      (node (ref "R71") (pin "2") (pinfunction "2_2") (pintype "passive"))
    )
    (net (code "60") (name "/USB_D_R_N") (class "Default")
      (node (ref "R72") (pin "1") (pinfunction "1_1") (pintype "passive"))
      (node (ref "U13") (pin "66") (pinfunction "UDB_DM_66") (pintype "bidirectional"))
    )
    (net (code "61") (name "/USB_D_R_P") (class "Default")
      (node (ref "R71") (pin "1") (pinfunction "1_1") (pintype "passive"))
      (node (ref "U13") (pin "67") (pinfunction "USB_DP_67") (pintype "bidirectional"))
    )
    (net (code "62") (name "/VREG_LX") (class "Default")
      (node (ref "L7") (pin "1") (pinfunction "1_1") (pintype "passive"))
      (node (ref "U13") (pin "63") (pinfunction "VREG_LX_63") (pintype "input"))
    )
    (net (code "63") (name "/W5500_CSn") (class "Default")
      (node (ref "U13") (pin "42") (pinfunction "GPIO33_42") (pintype "bidirectional"))
    )
    (net (code "64") (name "/W5500_INTn") (class "Default")
      (node (ref "R2") (pin "1") (pinfunction "1_1") (pintype "passive"))
      (node (ref "U13") (pin "26") (pinfunction "GPIO25_26") (pintype "bidirectional"))
    )
    (net (code "65") (name "/X_LIM") (class "Default")
      (node (ref "U13") (pin "47") (pinfunction "GPIO38_47") (pintype "bidirectional"))
    )
    (net (code "66") (name "/Y_LIM") (class "Default")
      (node (ref "U13") (pin "46") (pinfunction "GPIO37_46") (pintype "bidirectional"))
    )
    (net (code "67") (name "/Z_LIM") (class "Default")
      (node (ref "U13") (pin "45") (pinfunction "GPIO36_45") (pintype "bidirectional"))
    )
    (net (code "68") (name "MCU_GND") (class "Default")
      (node (ref "C105") (pin "1") (pinfunction "1_1") (pintype "passive"))
      (node (ref "C106") (pin "1") (pinfunction "1_1") (pintype "passive"))
      (node (ref "C115") (pin "1") (pinfunction "1_1") (pintype "passive"))
      (node (ref "C116") (pin "1") (pinfunction "1_1") (pintype "passive"))
      (node (ref "C41") (pin "1") (pinfunction "1_1") (pintype "passive"))
      (node (ref "C42") (pin "1") (pinfunction "1_1") (pintype "passive"))
      (node (ref "C43") (pin "2") (pinfunction "2_2") (pintype "passive"))
      (node (ref "C44") (pin "1") (pinfunction "1_1") (pintype "passive"))
      (node (ref "C5") (pin "1") (pinfunction "1_1") (pintype "passive"))
      (node (ref "C53") (pin "1") (pinfunction "1_1") (pintype "passive"))
      (node (ref "C57") (pin "1") (pinfunction "1_1") (pintype "passive"))
      (node (ref "C59") (pin "2") (pinfunction "2_2") (pintype "passive"))
      (node (ref "C61") (pin "1") (pinfunction "1_1") (pintype "passive"))
      (node (ref "C63") (pin "1") (pinfunction "1_1") (pintype "passive"))
      (node (ref "C64") (pin "1") (pinfunction "1_1") (pintype "passive"))
      (node (ref "C65") (pin "1") (pinfunction "1_1") (pintype "passive"))
      (node (ref "C66") (pin "1") (pinfunction "1_1") (pintype "passive"))
      (node (ref "C67") (pin "1") (pinfunction "1_1") (pintype "passive"))
      (node (ref "C68") (pin "1") (pinfunction "1_1") (pintype "passive"))
      (node (ref "C69") (pin "1") (pinfunction "1_1") (pintype "passive"))
      (node (ref "C70") (pin "1") (pinfunction "1_1") (pintype "passive"))
      (node (ref "C71") (pin "1") (pinfunction "1_1") (pintype "passive"))
      (node (ref "C72") (pin "1") (pinfunction "1_1") (pintype "passive"))
      (node (ref "C73") (pin "1") (pinfunction "1_1") (pintype "passive"))
      (node (ref "C74") (pin "1") (pinfunction "1_1") (pintype "passive"))
      (node (ref "C75") (pin "1") (pinfunction "1_1") (pintype "passive"))
      (node (ref "C76") (pin "1") (pinfunction "1_1") (pintype "passive"))
      (node (ref "C77") (pin "1") (pinfunction "1_1") (pintype "passive"))
      (node (ref "C78") (pin "1") (pinfunction "1_1") (pintype "passive"))
      (node (ref "C79") (pin "1") (pinfunction "1_1") (pintype "passive"))
      (node (ref "C9") (pin "1") (pinfunction "1_1") (pintype "passive"))
      (node (ref "J7") (pin "1") (pinfunction "1_1") (pintype "passive"))
      (node (ref "L4") (pin "4") (pinfunction "GND_4") (pintype "passive"))
      (node (ref "P9") (pin "3") (pinfunction "3_3") (pintype "passive"))
      (node (ref "P9") (pin "5") (pinfunction "5_5") (pintype "passive"))
      (node (ref "R103") (pin "1") (pinfunction "1_1") (pintype "passive"))
      (node (ref "SD1") (pin "11") (pinfunction "SHLD_11") (pintype "passive"))
      (node (ref "SD1") (pin "12") (pinfunction "SHLD_12") (pintype "passive"))
      (node (ref "SD1") (pin "13") (pinfunction "SHLD_13") (pintype "passive"))
      (node (ref "SD1") (pin "14") (pinfunction "SHLD_14") (pintype "passive"))
      (node (ref "SD1") (pin "6") (pinfunction "VSS_6") (pintype "passive"))
      (node (ref "SW3") (pin "2") (pinfunction "2_2") (pintype "passive"))
      (node (ref "SW4") (pin "2") (pinfunction "2_2") (pintype "passive"))
      (node (ref "U13") (pin "62") (pinfunction "VREG_PGND_62") (pintype "passive"))
      (node (ref "U13") (pin "81") (pinfunction "GND_PAD_81") (pintype "passive"))
      (node (ref "U26") (pin "2") (pinfunction "GND_2") (pintype "power_in"))
      (node (ref "U27") (pin "1") (pinfunction "A0_1") (pintype "input"))
      (node (ref "U27") (pin "2") (pinfunction "A1_2") (pintype "input"))
      (node (ref "U27") (pin "3") (pinfunction "A2_3") (pintype "input"))
      (node (ref "U27") (pin "4") (pinfunction "VSS_4") (pintype "power_in"))
      (node (ref "U27") (pin "7") (pinfunction "WP_7") (pintype "input"))
      (node (ref "Y2") (pin "2") (pinfunction "GND_1_2") (pintype "passive"))
      (node (ref "Y2") (pin "4") (pinfunction "GND_2_4") (pintype "passive"))
    )
    (net (code "69") (name "Net-(J7-Pad2)") (class "Default")
      (node (ref "J7") (pin "2") (pinfunction "2_2") (pintype "passive"))
      (node (ref "R104") (pin "1") (pinfunction "1_1") (pintype "passive"))
    )
    (net (code "70") (name "Net-(SD1-DAT1)") (class "Default")
      (node (ref "R106") (pin "1") (pinfunction "1_1") (pintype "passive"))
      (node (ref "SD1") (pin "8") (pinfunction "DAT1_8") (pintype "passive"))
    )
    (net (code "71") (name "Net-(SD1-DAT2)") (class "Default")
      (node (ref "R110") (pin "1") (pinfunction "1_1") (pintype "passive"))
      (node (ref "SD1") (pin "1") (pinfunction "DAT2_1") (pintype "passive"))
    )
    (net (code "72") (name "Net-(U13A-GPIO0)") (class "Default")
      (node (ref "R58") (pin "1") (pinfunction "1_1") (pintype "passive"))
      (node (ref "U13") (pin "77") (pinfunction "GPIO0_77") (pintype "bidirectional"))
    )
    (net (code "73") (name "Net-(U13A-GPIO2)") (class "Default")
      (node (ref "R17") (pin "1") (pinfunction "1_1") (pintype "passive"))
      (node (ref "U13") (pin "79") (pinfunction "GPIO2_79") (pintype "bidirectional"))
    )
    (net (code "74") (name "Net-(U13A-GPIO3)") (class "Default")
      (node (ref "R83") (pin "1") (pinfunction "1_1") (pintype "passive"))
      (node (ref "U13") (pin "80") (pinfunction "GPIO3_80") (pintype "bidirectional"))
    )
    (net (code "75") (name "Net-(U13A-GPIO40_AD0)") (class "Default")
      (node (ref "R79") (pin "2") (pinfunction "2_2") (pintype "passive"))
      (node (ref "U13") (pin "49") (pinfunction "GPIO40_AD0_49") (pintype "bidirectional"))
    )
    (net (code "76") (name "Net-(U13A-GPIO42_AD2)") (class "Default")
      (node (ref "R44") (pin "2") (pinfunction "2_2") (pintype "passive"))
      (node (ref "U13") (pin "53") (pinfunction "GPIO42_AD2_53") (pintype "bidirectional"))
    )
    (net (code "77") (name "Net-(U13A-GPIO43_AD3)") (class "Default")
      (node (ref "R43") (pin "2") (pinfunction "2_2") (pintype "passive"))
      (node (ref "U13") (pin "54") (pinfunction "GPIO43_AD3_54") (pintype "bidirectional"))
    )
    (net (code "78") (name "Net-(U13C-VREG_AVDD)") (class "Default")
      (node (ref "C64") (pin "2") (pinfunction "2_2") (pintype "passive"))
      (node (ref "R51") (pin "1") (pinfunction "1_1") (pintype "passive"))
      (node (ref "U13") (pin "61") (pinfunction "VREG_AVDD_61") (pintype "passive"))
    )
    (net (code "79") (name "Net-(U26-ADJ)") (class "Default")
      (node (ref "C104") (pin "1") (pinfunction "1_1") (pintype "passive"))
      (node (ref "R100") (pin "1") (pinfunction "1_1") (pintype "passive"))
      (node (ref "R103") (pin "2") (pinfunction "2_2") (pintype "passive"))
      (node (ref "R104") (pin "2") (pinfunction "2_2") (pintype "passive"))
      (node (ref "U26") (pin "4") (pinfunction "ADJ_4") (pintype "passive"))
    )
    (net (code "80") (name "Net-(U26-VOUT)") (class "Default")
      (node (ref "C104") (pin "2") (pinfunction "2_2") (pintype "passive"))
      (node (ref "R100") (pin "2") (pinfunction "2_2") (pintype "passive"))
      (node (ref "R105") (pin "1") (pinfunction "1_1") (pintype "passive"))
      (node (ref "U26") (pin "5") (pinfunction "VOUT_5") (pintype "power_in"))
    )
    (net (code "81") (name "Net-(Y2-CRYSTAL_2)") (class "Default")
      (node (ref "C59") (pin "1") (pinfunction "1_1") (pintype "passive"))
      (node (ref "R28") (pin "1") (pinfunction "1_1") (pintype "passive"))
      (node (ref "Y2") (pin "3") (pinfunction "CRYSTAL_2_3") (pintype "passive"))
    )
    (net (code "82") (name "unconnected-(P9-Pad6)") (class "Default")
      (node (ref "P9") (pin "6") (pinfunction "6_6") (pintype "passive"))
    )
    (net (code "83") (name "unconnected-(P9-Pad7)") (class "Default")
      (node (ref "P9") (pin "7") (pinfunction "7_7") (pintype "passive"))
    )
    (net (code "84") (name "unconnected-(P9-Pad8)") (class "Default")
      (node (ref "P9") (pin "8") (pinfunction "8_8") (pintype "passive"))
    )
    (net (code "85") (name "unconnected-(P9-Pad9)") (class "Default")
      (node (ref "P9") (pin "9") (pinfunction "9_9") (pintype "passive"))
    )
    (net (code "86") (name "unconnected-(SD1-CD_A-Pad9)") (class "Default")
      (node (ref "SD1") (pin "9") (pinfunction "CD_A_9") (pintype "passive"))
    )
    (net (code "87") (name "unconnected-(SD1-CD_B-Pad10)") (class "Default")
      (node (ref "SD1") (pin "10") (pinfunction "CD_B_10") (pintype "passive"))
    )
    (net (code "88") (name "unconnected-(SW3-Pad3)") (class "Default")
      (node (ref "SW3") (pin "3") (pinfunction "3_3") (pintype "passive"))
    )
    (net (code "89") (name "unconnected-(SW3-PadMP1)") (class "Default")
      (node (ref "SW3") (pin "MP1") (pinfunction "MP1_MP1") (pintype "passive"))
    )
    (net (code "90") (name "unconnected-(SW3-PadMP2)") (class "Default")
      (node (ref "SW3") (pin "MP2") (pinfunction "MP2_MP2") (pintype "passive"))
    )
    (net (code "91") (name "unconnected-(SW4-PadMP1)") (class "Default")
      (node (ref "SW4") (pin "MP1") (pinfunction "MP1_MP1") (pintype "passive"))
    )
    (net (code "92") (name "unconnected-(SW4-PadMP2)") (class "Default")
      (node (ref "SW4") (pin "MP2") (pinfunction "MP2_MP2") (pintype "passive"))
    )
  )
)
